# iac_driver.net
KiCad netlist of a schematic drawn in EAGLE
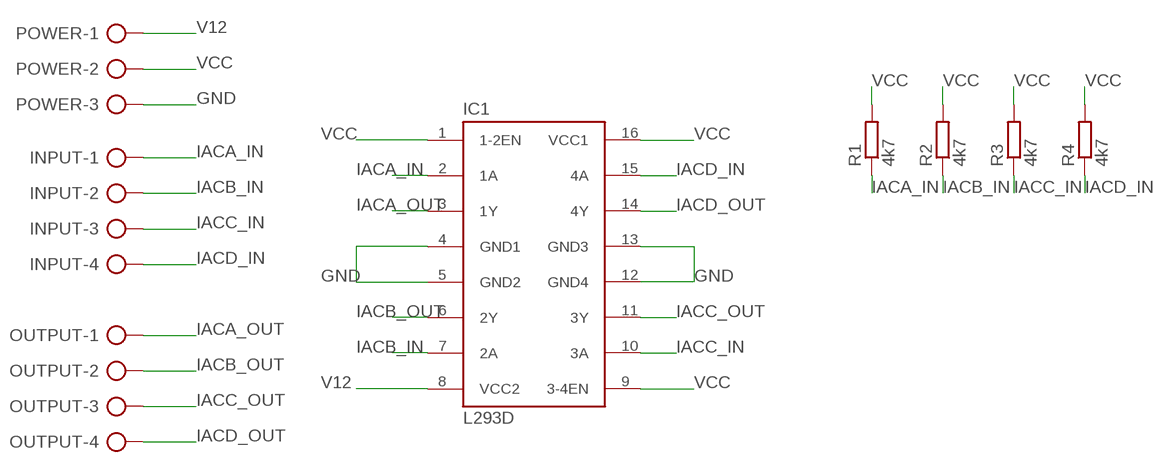
[diagram p0: schematic, sheet 1]

(export (version "E")
  (design (tool "Eeschema 10.0.6"))
  (components
    (comp (ref "IC1")
      (value "L293D")
      (footprint "eagle-import:DIL16")
      (libsource (lib "eagle-import") (part "L293D"))
    )
    (comp (ref "INPUT")
      (value "AK500/4")
      (footprint "eagle-import:AK500_4")
      (libsource (lib "eagle-import") (part "AK500/4"))
    )
    (comp (ref "OUTPUT")
      (value "AK500/4")
      (footprint "eagle-import:AK500_4")
      (libsource (lib "eagle-import") (part "AK500/4"))
    )
    (comp (ref "POWER")
      (value "AK500/3")
      (footprint "eagle-import:AK500_3")
      (libsource (lib "eagle-import") (part "AK500/3"))
    )
    (comp (ref "R1")
      (value "4k7")
      (footprint "eagle-import:0204_7")
      (libsource (lib "eagle-import") (part "R-EU_0204/7"))
    )
    (comp (ref "R2")
      (value "4k7")
      (footprint "eagle-import:0204_7")
      (libsource (lib "eagle-import") (part "R-EU_0204/7"))
    )
    (comp (ref "R3")
      (value "4k7")
      (footprint "eagle-import:0204_7")
      (libsource (lib "eagle-import") (part "R-EU_0204/7"))
    )
    (comp (ref "R4")
      (value "4k7")
      (footprint "eagle-import:0204_7")
      (libsource (lib "eagle-import") (part "R-EU_0204/7"))
    )
  )
  (nets
    (net (code "1") (name "/GND") (class "Default")
      (node (ref "IC1") (pin "12") (pinfunction "GND4_12") (pintype "power_in"))
      (node (ref "IC1") (pin "13") (pinfunction "GND3_13") (pintype "power_in"))
      (node (ref "IC1") (pin "4") (pinfunction "GND1_4") (pintype "power_in"))
      (node (ref "IC1") (pin "5") (pinfunction "GND2_5") (pintype "power_in"))
      (node (ref "POWER") (pin "3") (pinfunction "KL_3") (pintype "passive"))
    )
    (net (code "2") (name "/IACA_IN") (class "Default")
      (node (ref "IC1") (pin "2") (pinfunction "1A_2") (pintype "input"))
      (node (ref "INPUT") (pin "1") (pinfunction "KL_1") (pintype "passive"))
      (node (ref "R1") (pin "1") (pinfunction "1_1") (pintype "passive"))
    )
    (net (code "3") (name "/IACA_OUT") (class "Default")
      (node (ref "IC1") (pin "3") (pinfunction "1Y_3") (pintype "output"))
      (node (ref "OUTPUT") (pin "1") (pinfunction "KL_1") (pintype "passive"))
    )
    (net (code "4") (name "/IACB_IN") (class "Default")
      (node (ref "IC1") (pin "7") (pinfunction "2A_7") (pintype "input"))
      (node (ref "INPUT") (pin "2") (pinfunction "KL_2") (pintype "passive"))
      (node (ref "R2") (pin "1") (pinfunction "1_1") (pintype "passive"))
    )
    (net (code "5") (name "/IACB_OUT") (class "Default")
      (node (ref "IC1") (pin "6") (pinfunction "2Y_6") (pintype "output"))
      (node (ref "OUTPUT") (pin "2") (pinfunction "KL_2") (pintype "passive"))
    )
    (net (code "6") (name "/IACC_IN") (class "Default")
      (node (ref "IC1") (pin "10") (pinfunction "3A_10") (pintype "input"))
      (node (ref "INPUT") (pin "3") (pinfunction "KL_3") (pintype "passive"))
      (node (ref "R3") (pin "1") (pinfunction "1_1") (pintype "passive"))
    )
    (net (code "7") (name "/IACC_OUT") (class "Default")
      (node (ref "IC1") (pin "11") (pinfunction "3Y_11") (pintype "output"))
      (node (ref "OUTPUT") (pin "3") (pinfunction "KL_3") (pintype "passive"))
    )
    (net (code "8") (name "/IACD_IN") (class "Default")
      (node (ref "IC1") (pin "15") (pinfunction "4A_15") (pintype "input"))
      (node (ref "INPUT") (pin "4") (pinfunction "KL_4") (pintype "passive"))
      (node (ref "R4") (pin "1") (pinfunction "1_1") (pintype "passive"))
    )
    (net (code "9") (name "/IACD_OUT") (class "Default")
      (node (ref "IC1") (pin "14") (pinfunction "4Y_14") (pintype "output"))
      (node (ref "OUTPUT") (pin "4") (pinfunction "KL_4") (pintype "passive"))
    )
    (net (code "10") (name "/V12") (class "Default")
      (node (ref "IC1") (pin "8") (pinfunction "VCC2_8") (pintype "power_in"))
      (node (ref "POWER") (pin "1") (pinfunction "KL_1") (pintype "passive"))
    )
    (net (code "11") (name "/VCC") (class "Default")
      (node (ref "IC1") (pin "1") (pinfunction "1-2EN_1") (pintype "input"))
      (node (ref "IC1") (pin "16") (pinfunction "VCC1_16") (pintype "power_in"))
      (node (ref "IC1") (pin "9") (pinfunction "3-4EN_9") (pintype "input"))
      (node (ref "POWER") (pin "2") (pinfunction "KL_2") (pintype "passive"))
      (node (ref "R1") (pin "2") (pinfunction "2_2") (pintype "passive"))
      (node (ref "R2") (pin "2") (pinfunction "2_2") (pintype "passive"))
      (node (ref "R3") (pin "2") (pinfunction "2_2") (pintype "passive"))
      (node (ref "R4") (pin "2") (pinfunction "2_2") (pintype "passive"))
    )
  )
)
